# Music_Box_Shield.net
KiCad netlist of a schematic drawn in Altium Designer
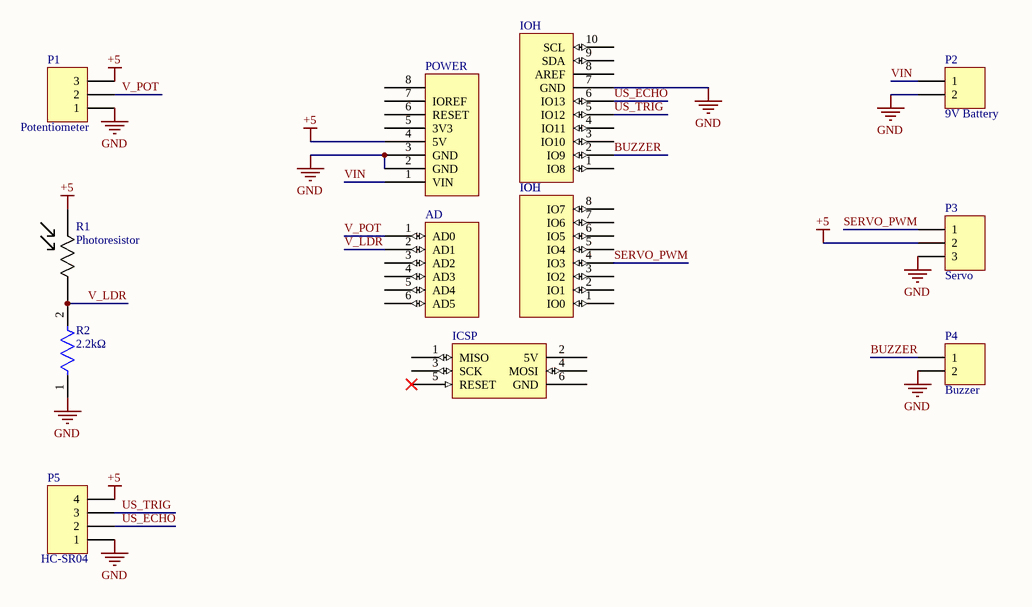
[diagram p0: Music Box Shield.SchDoc]

(export (version "E")
  (design (tool "Eeschema 10.0.6"))
  (components
    (comp (ref "AD")
      (value "AD")
      (footprint "Header:Header 6x1 8.5mm")
      (libsource (lib "Header") (part "AD"))
    )
    (comp (ref "ICSP") (value "ICSP") (footprint "ICSP") (libsource (lib "Header") (part "ICSP")))
    (comp (ref "IOH")
      (value "IOH")
      (footprint "Header:Header 10x1 8.5mm")
      (libsource (lib "Header") (part "IOH"))
    )
    (comp (ref "IOL") (value "IOL") (footprint "Header 8x1 8.5mm") (libsource (lib "Header") (part "IOL")))
    (comp (ref "P1")
      (value "Potentiometer")
      (footprint "HDR1X3")
      (description "Header, 3-Pin")
      (fields (field (name "PUBLISHER") "Altium Limited"))
      (libsource (lib "University of Toronto Aerospace Team") (part "Header 3H"))
    )
    (comp (ref "P2")
      (value "9V Battery")
      (footprint "HDR1X2")
      (description "Header, 2-Pin")
      (fields (field (name "PUBLISHER") "Altium Limited"))
      (libsource (lib "University of Toronto Aerospace Team") (part "Header 2H"))
    )
    (comp (ref "P3")
      (value "Servo")
      (footprint "HDR1X3")
      (description "Header, 3-Pin")
      (fields (field (name "PUBLISHER") "Altium Limited"))
      (libsource (lib "") (part "Header 3H_1"))
    )
    (comp (ref "P4")
      (value "Buzzer")
      (footprint "HDR1X2")
      (description "Header, 2-Pin")
      (fields (field (name "PUBLISHER") "Altium Limited"))
      (libsource (lib "University of Toronto Aerospace Team") (part "Header 2H"))
    )
    (comp (ref "P5")
      (value "HC-SR04")
      (footprint "HDR1X4")
      (description "Header, 4-Pin")
      (fields (field (name "PUBLISHER") "Altium Limited"))
      (libsource (lib "University of Toronto Aerospace Team") (part "Header 4H"))
    )
    (comp (ref "POWER")
      (value "POWER_UNO")
      (footprint "Header 8x1 8.5mm")
      (libsource (lib "Header") (part "POWER_UNO"))
    )
    (comp (ref "R1")
      (value "Photoresistor")
      (footprint "5mm Photoresistor")
      (description "No Description Available")
      (libsource (lib "Library") (part "Photoresistor"))
    )
    (comp (ref "R2")
      (value "CF18JT2K20")
      (footprint "FP-CF18-MFG")
      (description "RES 2.2K OHM 1/8W 5% CF AXIAL")
      (fields
        (field (name "OCTOPART") "https://octopart.com/cf18jt2k20-stackpole+electronics-19205714")
        (field (name "TOLERANCE") "5%")
        (field (name "RESISTANCE") "2.2kΩ")
      )
      (libsource (lib "Altium Content Vault") (part "1029c3af85768c4190bb7ad29bc67b5"))
    )
  )
  (nets
    (net (code "1") (name "+5") (class "Default")
      (node (ref "P1") (pin "3") (pinfunction "3_3") (pintype "passive"))
      (node (ref "P3") (pin "2") (pinfunction "2_2") (pintype "passive"))
      (node (ref "P5") (pin "4") (pinfunction "4_4") (pintype "passive"))
      (node (ref "POWER") (pin "4") (pinfunction "5V_4") (pintype "power_in"))
      (node (ref "R1") (pin "2") (pintype "passive"))
    )
    (net (code "3") (name "/BUZZER") (class "Default")
      (node (ref "IOH") (pin "2") (pinfunction "IO9_2") (pintype "bidirectional"))
      (node (ref "P4") (pin "1") (pinfunction "1_1") (pintype "passive"))
    )
    (net (code "4") (name "/SERVO_PWM") (class "Default")
      (node (ref "IOL") (pin "4") (pinfunction "IO3_4") (pintype "bidirectional"))
      (node (ref "P3") (pin "1") (pinfunction "1_1") (pintype "passive"))
    )
    (net (code "5") (name "/US_ECHO") (class "Default")
      (node (ref "IOH") (pin "6") (pinfunction "IO13_6") (pintype "bidirectional"))
      (node (ref "P5") (pin "2") (pinfunction "2_2") (pintype "passive"))
    )
    (net (code "6") (name "/US_TRIG") (class "Default")
      (node (ref "IOH") (pin "5") (pinfunction "IO12_5") (pintype "bidirectional"))
      (node (ref "P5") (pin "3") (pinfunction "3_3") (pintype "passive"))
    )
    (net (code "7") (name "/VIN") (class "Default")
      (node (ref "P2") (pin "1") (pinfunction "1_1") (pintype "passive"))
      (node (ref "POWER") (pin "1") (pinfunction "VIN_1") (pintype "power_in"))
    )
    (net (code "8") (name "/V_LDR") (class "Default")
      (node (ref "AD") (pin "2") (pinfunction "AD1_2") (pintype "bidirectional"))
      (node (ref "R1") (pin "1") (pintype "passive"))
      (node (ref "R2") (pin "2") (pinfunction "2_2") (pintype "passive"))
    )
    (net (code "9") (name "/V_POT") (class "Default")
      (node (ref "AD") (pin "1") (pinfunction "AD0_1") (pintype "bidirectional"))
      (node (ref "P1") (pin "2") (pinfunction "2_2") (pintype "passive"))
    )
    (net (code "10") (name "GND") (class "Default")
      (node (ref "IOH") (pin "7") (pinfunction "GND_7") (pintype "power_in"))
      (node (ref "P1") (pin "1") (pinfunction "1_1") (pintype "passive"))
      (node (ref "P2") (pin "2") (pinfunction "2_2") (pintype "passive"))
      (node (ref "P3") (pin "3") (pinfunction "3_3") (pintype "passive"))
      (node (ref "P4") (pin "2") (pinfunction "2_2") (pintype "passive"))
      (node (ref "P5") (pin "1") (pinfunction "1_1") (pintype "passive"))
      (node (ref "POWER") (pin "2") (pinfunction "GND_2") (pintype "power_in"))
      (node (ref "POWER") (pin "3") (pinfunction "GND_3") (pintype "power_in"))
      (node (ref "R2") (pin "1") (pinfunction "1_1") (pintype "passive"))
    )
    (net (code "11") (name "unconnected-(AD-AD2-Pad3)") (class "Default")
      (node (ref "AD") (pin "3") (pinfunction "AD2_3") (pintype "bidirectional"))
    )
    (net (code "12") (name "unconnected-(AD-AD3-Pad4)") (class "Default")
      (node (ref "AD") (pin "4") (pinfunction "AD3_4") (pintype "bidirectional"))
    )
    (net (code "13") (name "unconnected-(AD-AD4-Pad5)") (class "Default")
      (node (ref "AD") (pin "5") (pinfunction "AD4_5") (pintype "bidirectional"))
    )
    (net (code "14") (name "unconnected-(AD-AD5-Pad6)") (class "Default")
      (node (ref "AD") (pin "6") (pinfunction "AD5_6") (pintype "bidirectional"))
    )
    (net (code "15") (name "unconnected-(ICSP-5V-Pad2)") (class "Default")
      (node (ref "ICSP") (pin "2") (pinfunction "5V_2") (pintype "power_in"))
    )
    (net (code "16") (name "unconnected-(ICSP-GND-Pad6)") (class "Default")
      (node (ref "ICSP") (pin "6") (pinfunction "GND_6") (pintype "power_in"))
    )
    (net (code "17") (name "unconnected-(ICSP-MISO-Pad1)") (class "Default")
      (node (ref "ICSP") (pin "1") (pinfunction "MISO_1") (pintype "bidirectional"))
    )
    (net (code "18") (name "unconnected-(ICSP-MOSI-Pad4)") (class "Default")
      (node (ref "ICSP") (pin "4") (pinfunction "MOSI_4") (pintype "bidirectional"))
    )
    (net (code "19") (name "unconnected-(ICSP-RESET-Pad5)") (class "Default")
      (node (ref "ICSP") (pin "5") (pinfunction "RESET_5") (pintype "input+no_connect"))
    )
    (net (code "20") (name "unconnected-(ICSP-SCK-Pad3)") (class "Default")
      (node (ref "ICSP") (pin "3") (pinfunction "SCK_3") (pintype "bidirectional"))
    )
    (net (code "21") (name "unconnected-(IOH-AREF-Pad8)") (class "Default")
      (node (ref "IOH") (pin "8") (pinfunction "AREF_8") (pintype "passive"))
    )
    (net (code "22") (name "unconnected-(IOH-IO8-Pad1)") (class "Default")
      (node (ref "IOH") (pin "1") (pinfunction "IO8_1") (pintype "bidirectional"))
    )
    (net (code "23") (name "unconnected-(IOH-IO10-Pad3)") (class "Default")
      (node (ref "IOH") (pin "3") (pinfunction "IO10_3") (pintype "bidirectional"))
    )
    (net (code "24") (name "unconnected-(IOH-IO11-Pad4)") (class "Default")
      (node (ref "IOH") (pin "4") (pinfunction "IO11_4") (pintype "bidirectional"))
    )
    (net (code "25") (name "unconnected-(IOH-SCL-Pad10)") (class "Default")
      (node (ref "IOH") (pin "10") (pinfunction "SCL_10") (pintype "bidirectional"))
    )
    (net (code "26") (name "unconnected-(IOH-SDA-Pad9)") (class "Default")
      (node (ref "IOH") (pin "9") (pinfunction "SDA_9") (pintype "bidirectional"))
    )
    (net (code "27") (name "unconnected-(IOL-IO0-Pad1)") (class "Default")
      (node (ref "IOL") (pin "1") (pinfunction "IO0_1") (pintype "bidirectional"))
    )
    (net (code "28") (name "unconnected-(IOL-IO1-Pad2)") (class "Default")
      (node (ref "IOL") (pin "2") (pinfunction "IO1_2") (pintype "bidirectional"))
    )
    (net (code "29") (name "unconnected-(IOL-IO2-Pad3)") (class "Default")
      (node (ref "IOL") (pin "3") (pinfunction "IO2_3") (pintype "bidirectional"))
    )
    (net (code "30") (name "unconnected-(IOL-IO4-Pad5)") (class "Default")
      (node (ref "IOL") (pin "5") (pinfunction "IO4_5") (pintype "bidirectional"))
    )
    (net (code "31") (name "unconnected-(IOL-IO5-Pad6)") (class "Default")
      (node (ref "IOL") (pin "6") (pinfunction "IO5_6") (pintype "bidirectional"))
    )
    (net (code "32") (name "unconnected-(IOL-IO6-Pad7)") (class "Default")
      (node (ref "IOL") (pin "7") (pinfunction "IO6_7") (pintype "bidirectional"))
    )
    (net (code "33") (name "unconnected-(IOL-IO7-Pad8)") (class "Default")
      (node (ref "IOL") (pin "8") (pinfunction "IO7_8") (pintype "bidirectional"))
    )
    (net (code "34") (name "unconnected-(POWER-3V3-Pad5)") (class "Default")
      (node (ref "POWER") (pin "5") (pinfunction "3V3_5") (pintype "power_in"))
    )
    (net (code "35") (name "unconnected-(POWER-IOREF-Pad7)") (class "Default")
      (node (ref "POWER") (pin "7") (pinfunction "IOREF_7") (pintype "power_in"))
    )
    (net (code "36") (name "unconnected-(POWER-Pad8)") (class "Default")
      (node (ref "POWER") (pin "8") (pintype "passive"))
    )
    (net (code "37") (name "unconnected-(POWER-RESET-Pad6)") (class "Default")
      (node (ref "POWER") (pin "6") (pinfunction "RESET_6") (pintype "passive"))
    )
  )
)
